# BlinkyBoard.net
KiCad netlist of a schematic drawn in EAGLE
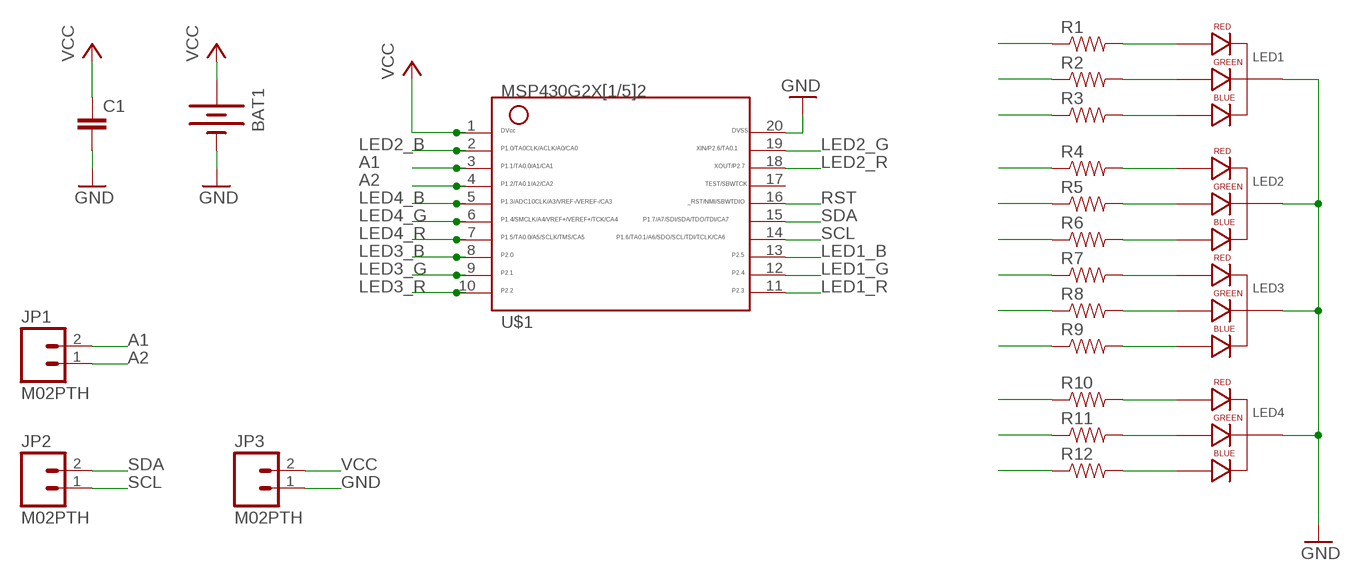
[diagram p0: schematic, sheet 1]

(export (version "E")
  (design (tool "Eeschema 10.0.6"))
  (components
    (comp (ref "BAT1")
      (value "BATTERY20PTH")
      (footprint "eagle-import:BATTCOM_20MM_PTH")
      (libsource (lib "eagle-import") (part "BATTERY20PTH"))
    )
    (comp (ref "C1")
      (value "CAPKIT")
      (footprint "eagle-import:CAP-PTH-SMALL-KIT")
      (libsource (lib "eagle-import") (part "CAPKIT"))
    )
    (comp (ref "JP1")
      (value "M02PTH")
      (footprint "eagle-import:1X02")
      (libsource (lib "eagle-import") (part "M02PTH"))
    )
    (comp (ref "JP2")
      (value "M02PTH")
      (footprint "eagle-import:1X02")
      (libsource (lib "eagle-import") (part "M02PTH"))
    )
    (comp (ref "JP3")
      (value "M02PTH")
      (footprint "eagle-import:1X02")
      (libsource (lib "eagle-import") (part "M02PTH"))
    )
    (comp (ref "LED1")
      (value "LED-RGB-CC-THRUDIFFUSE")
      (footprint "eagle-import:LED-RGB-THRU")
      (libsource (lib "eagle-import") (part "LED-RGB-CC-THRUDIFFUSE"))
    )
    (comp (ref "LED2")
      (value "LED-RGB-CC-THRUDIFFUSE")
      (footprint "eagle-import:LED-RGB-THRU")
      (libsource (lib "eagle-import") (part "LED-RGB-CC-THRUDIFFUSE"))
    )
    (comp (ref "LED3")
      (value "LED-RGB-CC-THRUDIFFUSE")
      (footprint "eagle-import:LED-RGB-THRU")
      (libsource (lib "eagle-import") (part "LED-RGB-CC-THRUDIFFUSE"))
    )
    (comp (ref "LED4")
      (value "LED-RGB-CC-THRUDIFFUSE")
      (footprint "eagle-import:LED-RGB-THRU")
      (libsource (lib "eagle-import") (part "LED-RGB-CC-THRUDIFFUSE"))
    )
    (comp (ref "R1")
      (value "RESISTORKIT")
      (footprint "eagle-import:AXIAL-0.3-KIT")
      (libsource (lib "eagle-import") (part "RESISTORKIT"))
    )
    (comp (ref "R2")
      (value "RESISTORKIT")
      (footprint "eagle-import:AXIAL-0.3-KIT")
      (libsource (lib "eagle-import") (part "RESISTORKIT"))
    )
    (comp (ref "R3")
      (value "RESISTORKIT")
      (footprint "eagle-import:AXIAL-0.3-KIT")
      (libsource (lib "eagle-import") (part "RESISTORKIT"))
    )
    (comp (ref "R4")
      (value "RESISTORKIT")
      (footprint "eagle-import:AXIAL-0.3-KIT")
      (libsource (lib "eagle-import") (part "RESISTORKIT"))
    )
    (comp (ref "R5")
      (value "RESISTORKIT")
      (footprint "eagle-import:AXIAL-0.3-KIT")
      (libsource (lib "eagle-import") (part "RESISTORKIT"))
    )
    (comp (ref "R6")
      (value "RESISTORKIT")
      (footprint "eagle-import:AXIAL-0.3-KIT")
      (libsource (lib "eagle-import") (part "RESISTORKIT"))
    )
    (comp (ref "R7")
      (value "RESISTORKIT")
      (footprint "eagle-import:AXIAL-0.3-KIT")
      (libsource (lib "eagle-import") (part "RESISTORKIT"))
    )
    (comp (ref "R8")
      (value "RESISTORKIT")
      (footprint "eagle-import:AXIAL-0.3-KIT")
      (libsource (lib "eagle-import") (part "RESISTORKIT"))
    )
    (comp (ref "R9")
      (value "RESISTORKIT")
      (footprint "eagle-import:AXIAL-0.3-KIT")
      (libsource (lib "eagle-import") (part "RESISTORKIT"))
    )
    (comp (ref "R10")
      (value "RESISTORKIT")
      (footprint "eagle-import:AXIAL-0.3-KIT")
      (libsource (lib "eagle-import") (part "RESISTORKIT"))
    )
    (comp (ref "R11")
      (value "RESISTORKIT")
      (footprint "eagle-import:AXIAL-0.3-KIT")
      (libsource (lib "eagle-import") (part "RESISTORKIT"))
    )
    (comp (ref "R12")
      (value "RESISTORKIT")
      (footprint "eagle-import:AXIAL-0.3-KIT")
      (libsource (lib "eagle-import") (part "RESISTORKIT"))
    )
    (comp (ref "U$1")
      (value "G2X[1/5]2---N20")
      (footprint "eagle-import:N20")
      (libsource (lib "eagle-import") (part "G2X[1/5]2---N20"))
    )
  )
  (nets
    (net (code "1") (name "/A1") (class "Default")
      (node (ref "JP1") (pin "2") (pinfunction "2_2") (pintype "passive"))
      (node (ref "U$1") (pin "3") (pinfunction "3_3") (pintype "bidirectional"))
    )
    (net (code "2") (name "/A2") (class "Default")
      (node (ref "JP1") (pin "1") (pinfunction "1_1") (pintype "passive"))
      (node (ref "U$1") (pin "4") (pinfunction "4_4") (pintype "bidirectional"))
    )
    (net (code "3") (name "/LED1_B") (class "Default")
      (node (ref "R3") (pin "P$1") (pinfunction "1_P$1") (pintype "passive"))
      (node (ref "U$1") (pin "13") (pinfunction "13_13") (pintype "bidirectional"))
    )
    (net (code "4") (name "/LED1_G") (class "Default")
      (node (ref "R2") (pin "P$1") (pinfunction "1_P$1") (pintype "passive"))
      (node (ref "U$1") (pin "12") (pinfunction "12_12") (pintype "bidirectional"))
    )
    (net (code "5") (name "/LED1_R") (class "Default")
      (node (ref "R1") (pin "P$1") (pinfunction "1_P$1") (pintype "passive"))
      (node (ref "U$1") (pin "11") (pinfunction "11_11") (pintype "bidirectional"))
    )
    (net (code "6") (name "/LED2_B") (class "Default")
      (node (ref "R6") (pin "P$1") (pinfunction "1_P$1") (pintype "passive"))
      (node (ref "U$1") (pin "2") (pinfunction "2_2") (pintype "bidirectional"))
    )
    (net (code "7") (name "/LED2_G") (class "Default")
      (node (ref "R5") (pin "P$1") (pinfunction "1_P$1") (pintype "passive"))
      (node (ref "U$1") (pin "19") (pinfunction "19_19") (pintype "bidirectional"))
    )
    (net (code "8") (name "/LED2_R") (class "Default")
      (node (ref "R4") (pin "P$1") (pinfunction "1_P$1") (pintype "passive"))
      (node (ref "U$1") (pin "18") (pinfunction "18_18") (pintype "bidirectional"))
    )
    (net (code "9") (name "/LED3_B") (class "Default")
      (node (ref "R9") (pin "P$1") (pinfunction "1_P$1") (pintype "passive"))
      (node (ref "U$1") (pin "8") (pinfunction "8_8") (pintype "bidirectional"))
    )
    (net (code "10") (name "/LED3_G") (class "Default")
      (node (ref "R8") (pin "P$1") (pinfunction "1_P$1") (pintype "passive"))
      (node (ref "U$1") (pin "9") (pinfunction "9_9") (pintype "bidirectional"))
    )
    (net (code "11") (name "/LED3_R") (class "Default")
      (node (ref "R7") (pin "P$1") (pinfunction "1_P$1") (pintype "passive"))
      (node (ref "U$1") (pin "10") (pinfunction "10_10") (pintype "bidirectional"))
    )
    (net (code "12") (name "/LED4_B") (class "Default")
      (node (ref "R12") (pin "P$1") (pinfunction "1_P$1") (pintype "passive"))
      (node (ref "U$1") (pin "5") (pinfunction "5_5") (pintype "bidirectional"))
    )
    (net (code "13") (name "/LED4_G") (class "Default")
      (node (ref "R11") (pin "P$1") (pinfunction "1_P$1") (pintype "passive"))
      (node (ref "U$1") (pin "6") (pinfunction "6_6") (pintype "bidirectional"))
    )
    (net (code "14") (name "/LED4_R") (class "Default")
      (node (ref "R10") (pin "P$1") (pinfunction "1_P$1") (pintype "passive"))
      (node (ref "U$1") (pin "7") (pinfunction "7_7") (pintype "bidirectional"))
    )
    (net (code "15") (name "/RST") (class "Default")
      (node (ref "U$1") (pin "16") (pinfunction "16_16") (pintype "bidirectional"))
    )
    (net (code "16") (name "/SCL") (class "Default")
      (node (ref "JP2") (pin "1") (pinfunction "1_1") (pintype "passive"))
      (node (ref "U$1") (pin "14") (pinfunction "14_14") (pintype "bidirectional"))
    )
    (net (code "17") (name "/SDA") (class "Default")
      (node (ref "JP2") (pin "2") (pinfunction "2_2") (pintype "passive"))
      (node (ref "U$1") (pin "15") (pinfunction "15_15") (pintype "bidirectional"))
    )
    (net (code "18") (name "GND") (class "Default")
      (node (ref "BAT1") (pin "2") (pinfunction "-_2") (pintype "power_in"))
      (node (ref "C1") (pin "2") (pinfunction "2_2") (pintype "passive"))
      (node (ref "JP3") (pin "1") (pinfunction "1_1") (pintype "passive"))
      (node (ref "LED1") (pin "2") (pinfunction "CATHODE_2") (pintype "bidirectional"))
      (node (ref "LED2") (pin "2") (pinfunction "CATHODE_2") (pintype "bidirectional"))
      (node (ref "LED3") (pin "2") (pinfunction "CATHODE_2") (pintype "bidirectional"))
      (node (ref "LED4") (pin "2") (pinfunction "CATHODE_2") (pintype "bidirectional"))
      (node (ref "U$1") (pin "20") (pinfunction "20_20") (pintype "bidirectional"))
    )
    (net (code "19") (name "Net-(LED1-BLUE_CATHODE)") (class "Default")
      (node (ref "LED1") (pin "4") (pinfunction "BLUE_CATHODE_4") (pintype "bidirectional"))
      (node (ref "R3") (pin "P$2") (pinfunction "2_P$2") (pintype "passive"))
    )
    (net (code "20") (name "Net-(LED1-GREEN_CATHODE)") (class "Default")
      (node (ref "LED1") (pin "3") (pinfunction "GREEN_CATHODE_3") (pintype "bidirectional"))
      (node (ref "R2") (pin "P$2") (pinfunction "2_P$2") (pintype "passive"))
    )
    (net (code "21") (name "Net-(LED1-RED_CATHODE)") (class "Default")
      (node (ref "LED1") (pin "1") (pinfunction "RED_CATHODE_1") (pintype "bidirectional"))
      (node (ref "R1") (pin "P$2") (pinfunction "2_P$2") (pintype "passive"))
    )
    (net (code "22") (name "Net-(LED2-BLUE_CATHODE)") (class "Default")
      (node (ref "LED2") (pin "4") (pinfunction "BLUE_CATHODE_4") (pintype "bidirectional"))
      (node (ref "R6") (pin "P$2") (pinfunction "2_P$2") (pintype "passive"))
    )
    (net (code "23") (name "Net-(LED2-GREEN_CATHODE)") (class "Default")
      (node (ref "LED2") (pin "3") (pinfunction "GREEN_CATHODE_3") (pintype "bidirectional"))
      (node (ref "R5") (pin "P$2") (pinfunction "2_P$2") (pintype "passive"))
    )
    (net (code "24") (name "Net-(LED2-RED_CATHODE)") (class "Default")
      (node (ref "LED2") (pin "1") (pinfunction "RED_CATHODE_1") (pintype "bidirectional"))
      (node (ref "R4") (pin "P$2") (pinfunction "2_P$2") (pintype "passive"))
    )
    (net (code "25") (name "Net-(LED3-BLUE_CATHODE)") (class "Default")
      (node (ref "LED3") (pin "4") (pinfunction "BLUE_CATHODE_4") (pintype "bidirectional"))
      (node (ref "R9") (pin "P$2") (pinfunction "2_P$2") (pintype "passive"))
    )
    (net (code "26") (name "Net-(LED3-GREEN_CATHODE)") (class "Default")
      (node (ref "LED3") (pin "3") (pinfunction "GREEN_CATHODE_3") (pintype "bidirectional"))
      (node (ref "R8") (pin "P$2") (pinfunction "2_P$2") (pintype "passive"))
    )
    (net (code "27") (name "Net-(LED3-RED_CATHODE)") (class "Default")
      (node (ref "LED3") (pin "1") (pinfunction "RED_CATHODE_1") (pintype "bidirectional"))
      (node (ref "R7") (pin "P$2") (pinfunction "2_P$2") (pintype "passive"))
    )
    (net (code "28") (name "Net-(LED4-BLUE_CATHODE)") (class "Default")
      (node (ref "LED4") (pin "4") (pinfunction "BLUE_CATHODE_4") (pintype "bidirectional"))
      (node (ref "R12") (pin "P$2") (pinfunction "2_P$2") (pintype "passive"))
    )
    (net (code "29") (name "Net-(LED4-GREEN_CATHODE)") (class "Default")
      (node (ref "LED4") (pin "3") (pinfunction "GREEN_CATHODE_3") (pintype "bidirectional"))
      (node (ref "R11") (pin "P$2") (pinfunction "2_P$2") (pintype "passive"))
    )
    (net (code "30") (name "Net-(LED4-RED_CATHODE)") (class "Default")
      (node (ref "LED4") (pin "1") (pinfunction "RED_CATHODE_1") (pintype "bidirectional"))
      (node (ref "R10") (pin "P$2") (pinfunction "2_P$2") (pintype "passive"))
    )
    (net (code "31") (name "VCC") (class "Default")
      (node (ref "BAT1") (pin "1") (pinfunction "+_1") (pintype "power_in"))
      (node (ref "C1") (pin "1") (pinfunction "1_1") (pintype "passive"))
      (node (ref "JP3") (pin "2") (pinfunction "2_2") (pintype "passive"))
      (node (ref "U$1") (pin "1") (pinfunction "1_1") (pintype "bidirectional"))
    )
    (net (code "32") (name "unconnected-(U$1-Pad17)") (class "Default")
      (node (ref "U$1") (pin "17") (pinfunction "17_17") (pintype "bidirectional"))
    )
  )
)
